# SCH_Controller_Altium.net
KiCad netlist of a schematic drawn in Altium Designer
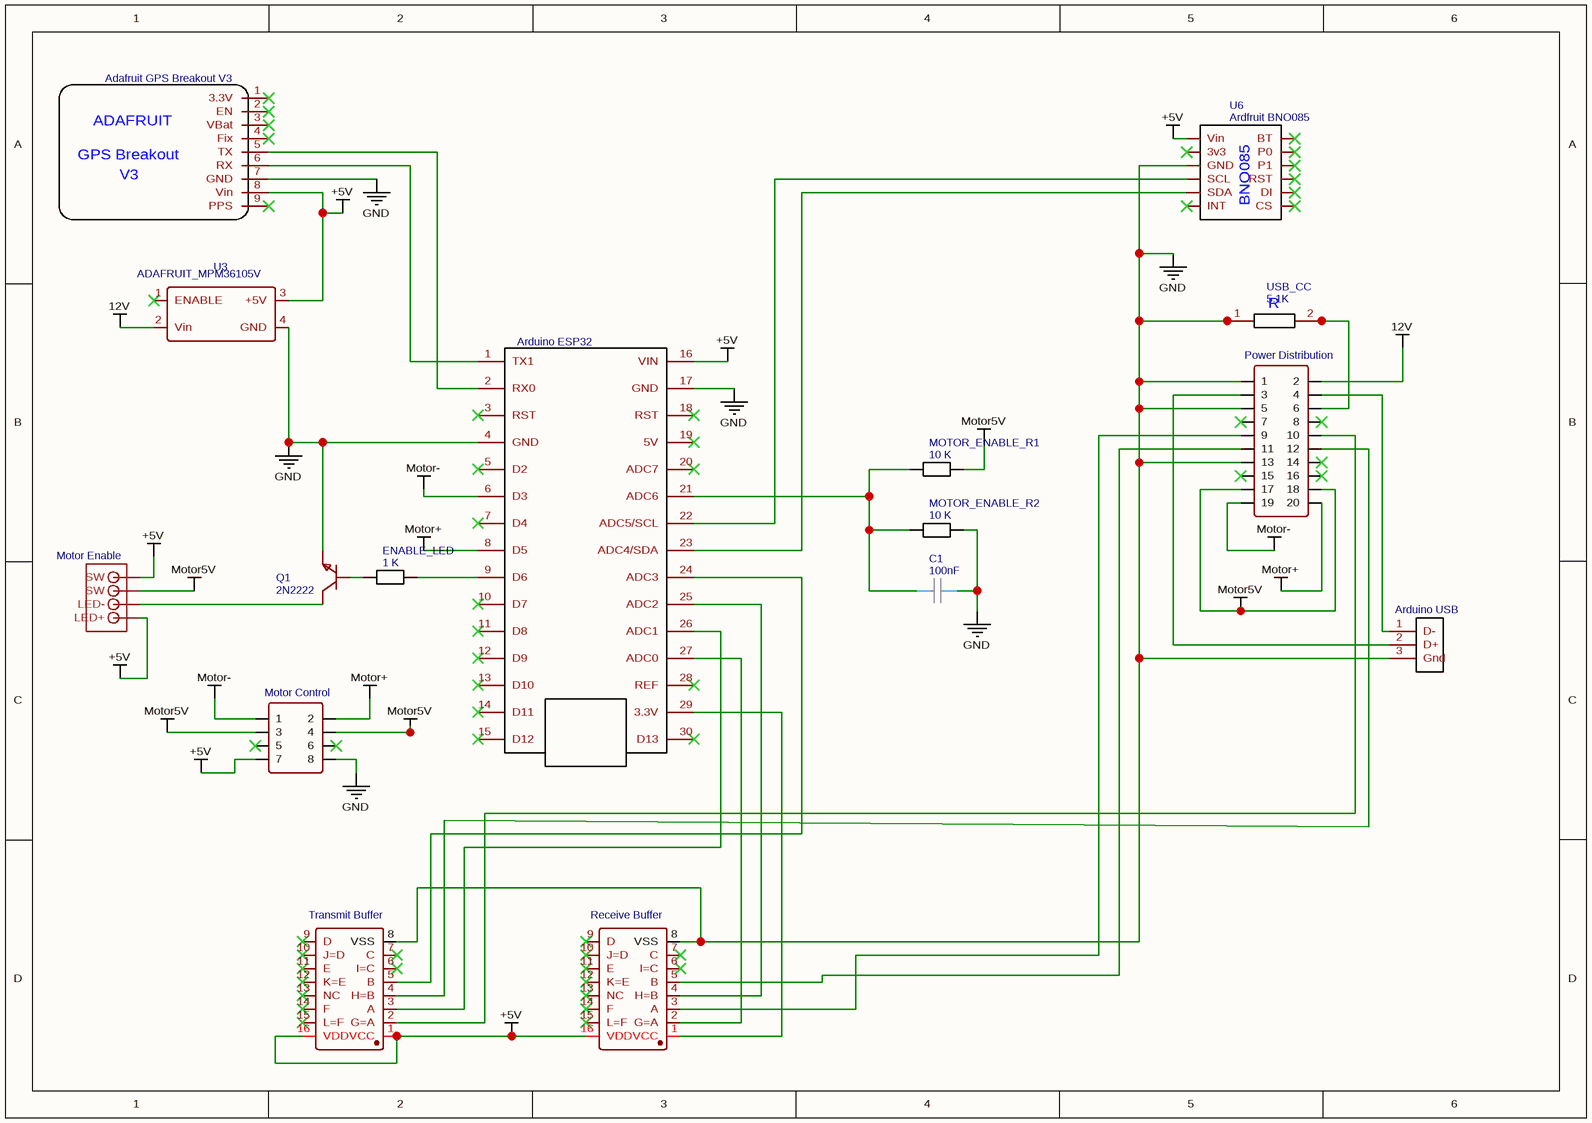
[diagram p0: SCH_Controller_Altium.schdoc]

(export (version "E")
  (design (tool "Eeschema 10.0.6"))
  (components
    (comp (ref "C1")
      (value "100nF")
      (fields (field (name "MANUFACTURER PART") "Capacitor_Ceramic") (field (name "CONTRIBUTOR") "gelo23"))
      (libsource (lib "altium-import") (part "root_1_100nF_"))
    )
    (comp (ref "ENABLE_LED")
      (value "1 K")
      (fields (field (name "CONTRIBUTOR") "roberto26"))
      (libsource (lib "altium-import") (part "root_3_1 K_"))
    )
    (comp (ref "HDR-M-2.54_2X4")
      (value "Motor Control")
      (fields (field (name "CONTRIBUTOR") "LCEDA_Lib"))
      (libsource (lib "altium-import") (part "root_0_Motor Control_"))
    )
    (comp (ref "JST_XH_1X3")
      (value "Arduino USB")
      (fields (field (name "CONTRIBUTOR") "GeMeMe"))
      (libsource (lib "altium-import") (part "root_0_Arduino USB_"))
    )
    (comp (ref "MOTOR_ENABLE_R1")
      (value "10 K")
      (fields (field (name "CONTRIBUTOR") "roberto26"))
      (libsource (lib "altium-import") (part "root_3_10 K_"))
    )
    (comp (ref "MOTOR_ENABLE_R2")
      (value "10 K")
      (fields (field (name "CONTRIBUTOR") "roberto26"))
      (libsource (lib "altium-import") (part "root_3_10 K_"))
    )
    (comp (ref "POWER1")
      (value "Power Distribution")
      (fields (field (name "CONTRIBUTOR") "LCEDA_Lib"))
      (libsource (lib "altium-import") (part "root_0_Power Distribution_"))
    )
    (comp (ref "Q1")
      (value "2N2222")
      (fields
        (field (name "MANUFACTURER") "ST(先科)")
        (field (name "MANUFACTURER PART") "2N2222A")
        (field (name "CONTRIBUTOR") "LCSC")
      )
      (libsource (lib "altium-import") (part "root_2_2N2222_"))
    )
    (comp (ref "U1")
      (value "Arduino ESP32")
      (fields (field (name "CONTRIBUTOR") "Nikolay Yanev"))
      (libsource (lib "altium-import") (part "root_0_Arduino ESP32_"))
    )
    (comp (ref "U2")
      (value "Receive Buffer")
      (fields
        (field (name "MANUFACTURER") "TI(德州仪器)")
        (field (name "MANUFACTURER PART") "CD4010BE")
        (field (name "CONTRIBUTOR") "LCSC")
      )
      (libsource (lib "altium-import") (part "root_2_Receive Buffer_"))
    )
    (comp (ref "U3")
      (value "ADAFRUIT_MPM36105V")
      (fields (field (name "CONTRIBUTOR") "Aidan Farley"))
      (libsource (lib "altium-import") (part "root_0_ADAFRUIT_MPM36105V_"))
    )
    (comp (ref "U4")
      (value "Adafruit GPS Breakout V3")
      (fields (field (name "MANUFACTURER PART") "New SchematicLib") (field (name "CONTRIBUTOR") "NiklasC"))
      (libsource (lib "altium-import") (part "root_0_Adafruit GPS Breakout V3_"))
    )
    (comp (ref "U5")
      (value "Transmit Buffer")
      (fields
        (field (name "MANUFACTURER") "TI(德州仪器)")
        (field (name "MANUFACTURER PART") "CD4010BE")
        (field (name "CONTRIBUTOR") "LCSC")
      )
      (libsource (lib "altium-import") (part "root_2_Transmit Buffer_"))
    )
    (comp (ref "U6")
      (value "Ardfruit BNO085")
      (fields (field (name "MANUFACTURER") "Ardfruit") (field (name "CONTRIBUTOR") "Ashok Dhaker"))
      (libsource (lib "altium-import") (part "root_0_Ardfruit BNO085_"))
    )
    (comp (ref "U7")
      (value "Motor Enable")
      (fields (field (name "CONTRIBUTOR") "Oleg0903"))
      (libsource (lib "altium-import") (part "root_0_Motor Enable_"))
    )
    (comp (ref "USB_CC")
      (value "5.1K")
      (fields
        (field (name "MANUFACTURER") "API Delevan")
        (field (name "MANUFACTURER PART") "4211R-13")
        (field (name "CONTRIBUTOR") "cwml")
      )
      (libsource (lib "altium-import") (part "root_0_5.1K_"))
    )
  )
  (nets
    (net (code "1") (name "+5V") (class "Default")
      (node (ref "HDR-M-2.54_2X4") (pin "7") (pinfunction "7_7") (pintype "passive"))
      (node (ref "U1") (pin "16") (pinfunction "VIN_16") (pintype "passive"))
      (node (ref "U2") (pin "16") (pinfunction "VDD_16") (pintype "passive"))
      (node (ref "U3") (pin "3") (pinfunction "+5V_3") (pintype "passive"))
      (node (ref "U4") (pin "8") (pinfunction "Vin_8") (pintype "passive"))
      (node (ref "U5") (pin "1") (pinfunction "VCC_1") (pintype "passive"))
      (node (ref "U5") (pin "16") (pinfunction "VDD_16") (pintype "passive"))
      (node (ref "U6") (pin "1") (pinfunction "Vin_1") (pintype "passive"))
      (node (ref "U7") (pin "P1") (pinfunction "SW_P1") (pintype "passive"))
      (node (ref "U7") (pin "P4") (pinfunction "LED+_P4") (pintype "passive"))
    )
    (net (code "2") (name "12V") (class "Default")
      (node (ref "POWER1") (pin "2") (pinfunction "2_2") (pintype "passive"))
      (node (ref "U3") (pin "2") (pinfunction "Vin_2") (pintype "passive"))
    )
    (net (code "3") (name "GND") (class "Default")
      (node (ref "C1") (pin "1") (pinfunction "1_1") (pintype "passive"))
      (node (ref "HDR-M-2.54_2X4") (pin "8") (pinfunction "8_8") (pintype "passive"))
      (node (ref "JST_XH_1X3") (pin "3") (pinfunction "Gnd_3") (pintype "passive"))
      (node (ref "MOTOR_ENABLE_R2") (pin "1") (pinfunction "1_1") (pintype "passive"))
      (node (ref "POWER1") (pin "1") (pinfunction "1_1") (pintype "passive"))
      (node (ref "POWER1") (pin "13") (pinfunction "13_13") (pintype "passive"))
      (node (ref "POWER1") (pin "5") (pinfunction "5_5") (pintype "passive"))
      (node (ref "Q1") (pin "1") (pinfunction "E_1") (pintype "passive"))
      (node (ref "U1") (pin "17") (pinfunction "GND_17") (pintype "passive"))
      (node (ref "U1") (pin "4") (pinfunction "GND_4") (pintype "passive"))
      (node (ref "U2") (pin "8") (pinfunction "VSS_8") (pintype "passive"))
      (node (ref "U3") (pin "4") (pinfunction "GND_4") (pintype "passive"))
      (node (ref "U4") (pin "7") (pinfunction "GND_7") (pintype "passive"))
      (node (ref "U5") (pin "8") (pinfunction "VSS_8") (pintype "passive"))
      (node (ref "U6") (pin "3") (pinfunction "GND_3") (pintype "passive"))
      (node (ref "USB_CC") (pin "1") (pinfunction "1_1") (pintype "passive"))
    )
    (net (code "4") (name "Motor+") (class "Default")
      (node (ref "HDR-M-2.54_2X4") (pin "2") (pinfunction "2_2") (pintype "passive"))
      (node (ref "POWER1") (pin "20") (pinfunction "20_20") (pintype "passive"))
      (node (ref "U1") (pin "8") (pinfunction "D5_8") (pintype "passive"))
    )
    (net (code "5") (name "Motor-") (class "Default")
      (node (ref "HDR-M-2.54_2X4") (pin "1") (pinfunction "1_1") (pintype "passive"))
      (node (ref "POWER1") (pin "19") (pinfunction "19_19") (pintype "passive"))
      (node (ref "U1") (pin "6") (pinfunction "D3_6") (pintype "passive"))
    )
    (net (code "6") (name "Motor5V") (class "Default")
      (node (ref "HDR-M-2.54_2X4") (pin "3") (pinfunction "3_3") (pintype "passive"))
      (node (ref "HDR-M-2.54_2X4") (pin "4") (pinfunction "4_4") (pintype "passive"))
      (node (ref "MOTOR_ENABLE_R1") (pin "1") (pinfunction "1_1") (pintype "passive"))
      (node (ref "POWER1") (pin "17") (pinfunction "17_17") (pintype "passive"))
      (node (ref "POWER1") (pin "18") (pinfunction "18_18") (pintype "passive"))
      (node (ref "U7") (pin "P2") (pinfunction "SW_P2") (pintype "passive"))
    )
    (net (code "7") (name "Net-(JST_XH_1X3-D+)") (class "Default")
      (node (ref "JST_XH_1X3") (pin "2") (pinfunction "D+_2") (pintype "passive"))
      (node (ref "POWER1") (pin "3") (pinfunction "3_3") (pintype "passive"))
    )
    (net (code "8") (name "Net-(JST_XH_1X3-D-)") (class "Default")
      (node (ref "JST_XH_1X3") (pin "1") (pinfunction "D-_1") (pintype "passive"))
      (node (ref "POWER1") (pin "4") (pinfunction "4_4") (pintype "passive"))
    )
    (net (code "9") (name "Net-(POWER1-Pad6)") (class "Default")
      (node (ref "POWER1") (pin "6") (pinfunction "6_6") (pintype "passive"))
      (node (ref "USB_CC") (pin "2") (pinfunction "2_2") (pintype "passive"))
    )
    (net (code "10") (name "Net-(Q1-B)") (class "Default")
      (node (ref "ENABLE_LED") (pin "2") (pinfunction "2_2") (pintype "passive"))
      (node (ref "Q1") (pin "2") (pinfunction "B_2") (pintype "passive"))
    )
    (net (code "11") (name "Net-(Q1-C)") (class "Default")
      (node (ref "Q1") (pin "3") (pinfunction "C_3") (pintype "passive"))
      (node (ref "U7") (pin "P3") (pinfunction "LED-_P3") (pintype "passive"))
    )
    (net (code "12") (name "Net-(U1-3.3V)") (class "Default")
      (node (ref "U1") (pin "29") (pinfunction "3.3V_29") (pintype "passive"))
      (node (ref "U2") (pin "1") (pinfunction "VCC_1") (pintype "passive"))
    )
    (net (code "13") (name "Net-(U1-ADC0)") (class "Default")
      (node (ref "U1") (pin "27") (pinfunction "ADC0_27") (pintype "passive"))
      (node (ref "U2") (pin "2") (pinfunction "G=A_2") (pintype "passive"))
    )
    (net (code "14") (name "Net-(U1-ADC1)") (class "Default")
      (node (ref "U1") (pin "26") (pinfunction "ADC1_26") (pintype "passive"))
      (node (ref "U5") (pin "3") (pinfunction "A_3") (pintype "passive"))
    )
    (net (code "15") (name "Net-(U1-ADC2)") (class "Default")
      (node (ref "U1") (pin "25") (pinfunction "ADC2_25") (pintype "passive"))
      (node (ref "U2") (pin "4") (pinfunction "H=B_4") (pintype "passive"))
    )
    (net (code "16") (name "Net-(U1-ADC3)") (class "Default")
      (node (ref "U1") (pin "24") (pinfunction "ADC3_24") (pintype "passive"))
      (node (ref "U5") (pin "5") (pinfunction "B_5") (pintype "passive"))
    )
    (net (code "17") (name "Net-(U1-ADC4{slash}SDA)") (class "Default")
      (node (ref "U1") (pin "23") (pinfunction "ADC4/SDA_23") (pintype "passive"))
      (node (ref "U6") (pin "5") (pinfunction "SDA_5") (pintype "passive"))
    )
    (net (code "18") (name "Net-(U1-ADC5{slash}SCL)") (class "Default")
      (node (ref "U1") (pin "22") (pinfunction "ADC5/SCL_22") (pintype "passive"))
      (node (ref "U6") (pin "4") (pinfunction "SCL_4") (pintype "passive"))
    )
    (net (code "19") (name "Net-(U1-ADC6)") (class "Default")
      (node (ref "C1") (pin "2") (pinfunction "2_2") (pintype "passive"))
      (node (ref "MOTOR_ENABLE_R1") (pin "2") (pinfunction "2_2") (pintype "passive"))
      (node (ref "MOTOR_ENABLE_R2") (pin "2") (pinfunction "2_2") (pintype "passive"))
      (node (ref "U1") (pin "21") (pinfunction "ADC6_21") (pintype "passive"))
    )
    (net (code "20") (name "Net-(U1-D6)") (class "Default")
      (node (ref "ENABLE_LED") (pin "1") (pinfunction "1_1") (pintype "passive"))
      (node (ref "U1") (pin "9") (pinfunction "D6_9") (pintype "passive"))
    )
    (net (code "21") (name "Net-(U1-RX0)") (class "Default")
      (node (ref "U1") (pin "2") (pinfunction "RX0_2") (pintype "passive"))
      (node (ref "U4") (pin "5") (pinfunction "TX_5") (pintype "passive"))
    )
    (net (code "22") (name "Net-(U1-TX1)") (class "Default")
      (node (ref "U1") (pin "1") (pinfunction "TX1_1") (pintype "passive"))
      (node (ref "U4") (pin "6") (pinfunction "RX_6") (pintype "passive"))
    )
    (net (code "23") (name "Net-(U2-A)") (class "Default")
      (node (ref "POWER1") (pin "9") (pinfunction "9_9") (pintype "passive"))
      (node (ref "U2") (pin "3") (pinfunction "A_3") (pintype "passive"))
    )
    (net (code "24") (name "Net-(U2-B)") (class "Default")
      (node (ref "POWER1") (pin "11") (pinfunction "11_11") (pintype "passive"))
      (node (ref "U2") (pin "5") (pinfunction "B_5") (pintype "passive"))
    )
    (net (code "25") (name "Net-(U5-G=A)") (class "Default")
      (node (ref "POWER1") (pin "10") (pinfunction "10_10") (pintype "passive"))
      (node (ref "U5") (pin "2") (pinfunction "G=A_2") (pintype "passive"))
    )
    (net (code "26") (name "Net-(U5-H=B)") (class "Default")
      (node (ref "POWER1") (pin "12") (pinfunction "12_12") (pintype "passive"))
      (node (ref "U5") (pin "4") (pinfunction "H=B_4") (pintype "passive"))
    )
    (net (code "27") (name "unconnected-(HDR-M-2.54_2X4-Pad5)") (class "Default")
      (node (ref "HDR-M-2.54_2X4") (pin "5") (pinfunction "5_5") (pintype "passive+no_connect"))
    )
    (net (code "28") (name "unconnected-(HDR-M-2.54_2X4-Pad6)") (class "Default")
      (node (ref "HDR-M-2.54_2X4") (pin "6") (pinfunction "6_6") (pintype "passive+no_connect"))
    )
    (net (code "29") (name "unconnected-(POWER1-Pad7)") (class "Default")
      (node (ref "POWER1") (pin "7") (pinfunction "7_7") (pintype "passive+no_connect"))
    )
    (net (code "30") (name "unconnected-(POWER1-Pad8)") (class "Default")
      (node (ref "POWER1") (pin "8") (pinfunction "8_8") (pintype "passive+no_connect"))
    )
    (net (code "31") (name "unconnected-(POWER1-Pad14)") (class "Default")
      (node (ref "POWER1") (pin "14") (pinfunction "14_14") (pintype "passive+no_connect"))
    )
    (net (code "32") (name "unconnected-(POWER1-Pad15)") (class "Default")
      (node (ref "POWER1") (pin "15") (pinfunction "15_15") (pintype "passive+no_connect"))
    )
    (net (code "33") (name "unconnected-(POWER1-Pad16)") (class "Default")
      (node (ref "POWER1") (pin "16") (pinfunction "16_16") (pintype "passive+no_connect"))
    )
    (net (code "34") (name "unconnected-(U1-5V-Pad19)") (class "Default")
      (node (ref "U1") (pin "19") (pinfunction "5V_19") (pintype "passive+no_connect"))
    )
    (net (code "35") (name "unconnected-(U1-ADC7-Pad20)") (class "Default")
      (node (ref "U1") (pin "20") (pinfunction "ADC7_20") (pintype "passive+no_connect"))
    )
    (net (code "36") (name "unconnected-(U1-D2-Pad5)") (class "Default")
      (node (ref "U1") (pin "5") (pinfunction "D2_5") (pintype "passive+no_connect"))
    )
    (net (code "37") (name "unconnected-(U1-D4-Pad7)") (class "Default")
      (node (ref "U1") (pin "7") (pinfunction "D4_7") (pintype "passive+no_connect"))
    )
    (net (code "38") (name "unconnected-(U1-D7-Pad10)") (class "Default")
      (node (ref "U1") (pin "10") (pinfunction "D7_10") (pintype "passive+no_connect"))
    )
    (net (code "39") (name "unconnected-(U1-D8-Pad11)") (class "Default")
      (node (ref "U1") (pin "11") (pinfunction "D8_11") (pintype "passive+no_connect"))
    )
    (net (code "40") (name "unconnected-(U1-D9-Pad12)") (class "Default")
      (node (ref "U1") (pin "12") (pinfunction "D9_12") (pintype "passive+no_connect"))
    )
    (net (code "41") (name "unconnected-(U1-D10-Pad13)") (class "Default")
      (node (ref "U1") (pin "13") (pinfunction "D10_13") (pintype "passive+no_connect"))
    )
    (net (code "42") (name "unconnected-(U1-D11-Pad14)") (class "Default")
      (node (ref "U1") (pin "14") (pinfunction "D11_14") (pintype "passive+no_connect"))
    )
    (net (code "43") (name "unconnected-(U1-D12-Pad15)") (class "Default")
      (node (ref "U1") (pin "15") (pinfunction "D12_15") (pintype "passive+no_connect"))
    )
    (net (code "44") (name "unconnected-(U1-D13-Pad30)") (class "Default")
      (node (ref "U1") (pin "30") (pinfunction "D13_30") (pintype "passive+no_connect"))
    )
    (net (code "45") (name "unconnected-(U1-REF-Pad28)") (class "Default")
      (node (ref "U1") (pin "28") (pinfunction "REF_28") (pintype "passive+no_connect"))
    )
    (net (code "46") (name "unconnected-(U1-RST-Pad3)") (class "Default")
      (node (ref "U1") (pin "3") (pinfunction "RST_3") (pintype "passive+no_connect"))
    )
    (net (code "47") (name "unconnected-(U1-RST-Pad18)") (class "Default")
      (node (ref "U1") (pin "18") (pinfunction "RST_18") (pintype "passive+no_connect"))
    )
    (net (code "48") (name "unconnected-(U2-C-Pad7)") (class "Default")
      (node (ref "U2") (pin "7") (pinfunction "C_7") (pintype "passive+no_connect"))
    )
    (net (code "49") (name "unconnected-(U2-D-Pad9)") (class "Default")
      (node (ref "U2") (pin "9") (pinfunction "D_9") (pintype "passive+no_connect"))
    )
    (net (code "50") (name "unconnected-(U2-E-Pad11)") (class "Default")
      (node (ref "U2") (pin "11") (pinfunction "E_11") (pintype "passive+no_connect"))
    )
    (net (code "51") (name "unconnected-(U2-F-Pad14)") (class "Default")
      (node (ref "U2") (pin "14") (pinfunction "F_14") (pintype "passive+no_connect"))
    )
    (net (code "52") (name "unconnected-(U2-I=C-Pad6)") (class "Default")
      (node (ref "U2") (pin "6") (pinfunction "I=C_6") (pintype "passive+no_connect"))
    )
    (net (code "53") (name "unconnected-(U2-J=D-Pad10)") (class "Default")
      (node (ref "U2") (pin "10") (pinfunction "J=D_10") (pintype "passive+no_connect"))
    )
    (net (code "54") (name "unconnected-(U2-K=E-Pad12)") (class "Default")
      (node (ref "U2") (pin "12") (pinfunction "K=E_12") (pintype "passive+no_connect"))
    )
    (net (code "55") (name "unconnected-(U2-L=F-Pad15)") (class "Default")
      (node (ref "U2") (pin "15") (pinfunction "L=F_15") (pintype "passive+no_connect"))
    )
    (net (code "56") (name "unconnected-(U2-NC-Pad13)") (class "Default")
      (node (ref "U2") (pin "13") (pinfunction "NC_13") (pintype "passive+no_connect"))
    )
    (net (code "57") (name "unconnected-(U3-ENABLE-Pad1)") (class "Default")
      (node (ref "U3") (pin "1") (pinfunction "ENABLE_1") (pintype "passive+no_connect"))
    )
    (net (code "58") (name "unconnected-(U4-3.3V-Pad1)") (class "Default")
      (node (ref "U4") (pin "1") (pinfunction "3.3V_1") (pintype "passive+no_connect"))
    )
    (net (code "59") (name "unconnected-(U4-EN-Pad2)") (class "Default")
      (node (ref "U4") (pin "2") (pinfunction "EN_2") (pintype "passive+no_connect"))
    )
    (net (code "60") (name "unconnected-(U4-Fix-Pad4)") (class "Default")
      (node (ref "U4") (pin "4") (pinfunction "Fix_4") (pintype "passive+no_connect"))
    )
    (net (code "61") (name "unconnected-(U4-PPS-Pad9)") (class "Default")
      (node (ref "U4") (pin "9") (pinfunction "PPS_9") (pintype "passive+no_connect"))
    )
    (net (code "62") (name "unconnected-(U4-VBat-Pad3)") (class "Default")
      (node (ref "U4") (pin "3") (pinfunction "VBat_3") (pintype "passive+no_connect"))
    )
    (net (code "63") (name "unconnected-(U5-C-Pad7)") (class "Default")
      (node (ref "U5") (pin "7") (pinfunction "C_7") (pintype "passive+no_connect"))
    )
    (net (code "64") (name "unconnected-(U5-D-Pad9)") (class "Default")
      (node (ref "U5") (pin "9") (pinfunction "D_9") (pintype "passive+no_connect"))
    )
    (net (code "65") (name "unconnected-(U5-E-Pad11)") (class "Default")
      (node (ref "U5") (pin "11") (pinfunction "E_11") (pintype "passive+no_connect"))
    )
    (net (code "66") (name "unconnected-(U5-F-Pad14)") (class "Default")
      (node (ref "U5") (pin "14") (pinfunction "F_14") (pintype "passive+no_connect"))
    )
    (net (code "67") (name "unconnected-(U5-I=C-Pad6)") (class "Default")
      (node (ref "U5") (pin "6") (pinfunction "I=C_6") (pintype "passive+no_connect"))
    )
    (net (code "68") (name "unconnected-(U5-J=D-Pad10)") (class "Default")
      (node (ref "U5") (pin "10") (pinfunction "J=D_10") (pintype "passive+no_connect"))
    )
    (net (code "69") (name "unconnected-(U5-K=E-Pad12)") (class "Default")
      (node (ref "U5") (pin "12") (pinfunction "K=E_12") (pintype "passive+no_connect"))
    )
    (net (code "70") (name "unconnected-(U5-L=F-Pad15)") (class "Default")
      (node (ref "U5") (pin "15") (pinfunction "L=F_15") (pintype "passive+no_connect"))
    )
    (net (code "71") (name "unconnected-(U5-NC-Pad13)") (class "Default")
      (node (ref "U5") (pin "13") (pinfunction "NC_13") (pintype "passive+no_connect"))
    )
    (net (code "72") (name "unconnected-(U6-3v3-Pad2)") (class "Default")
      (node (ref "U6") (pin "2") (pinfunction "3v3_2") (pintype "passive+no_connect"))
    )
    (net (code "73") (name "unconnected-(U6-BT-Pad12)") (class "Default")
      (node (ref "U6") (pin "12") (pinfunction "BT_12") (pintype "passive+no_connect"))
    )
    (net (code "74") (name "unconnected-(U6-CS-Pad7)") (class "Default")
      (node (ref "U6") (pin "7") (pinfunction "CS_7") (pintype "passive+no_connect"))
    )
    (net (code "75") (name "unconnected-(U6-DI-Pad8)") (class "Default")
      (node (ref "U6") (pin "8") (pinfunction "DI_8") (pintype "passive+no_connect"))
    )
    (net (code "76") (name "unconnected-(U6-INT-Pad6)") (class "Default")
      (node (ref "U6") (pin "6") (pinfunction "INT_6") (pintype "passive+no_connect"))
    )
    (net (code "77") (name "unconnected-(U6-P0-Pad11)") (class "Default")
      (node (ref "U6") (pin "11") (pinfunction "P0_11") (pintype "passive+no_connect"))
    )
    (net (code "78") (name "unconnected-(U6-P1-Pad10)") (class "Default")
      (node (ref "U6") (pin "10") (pinfunction "P1_10") (pintype "passive+no_connect"))
    )
    (net (code "79") (name "unconnected-(U6-RST-Pad9)") (class "Default")
      (node (ref "U6") (pin "9") (pinfunction "RST_9") (pintype "passive+no_connect"))
    )
  )
)
